# Voltage_Sense_0-30V.net
KiCad netlist of a schematic drawn in Altium Designer
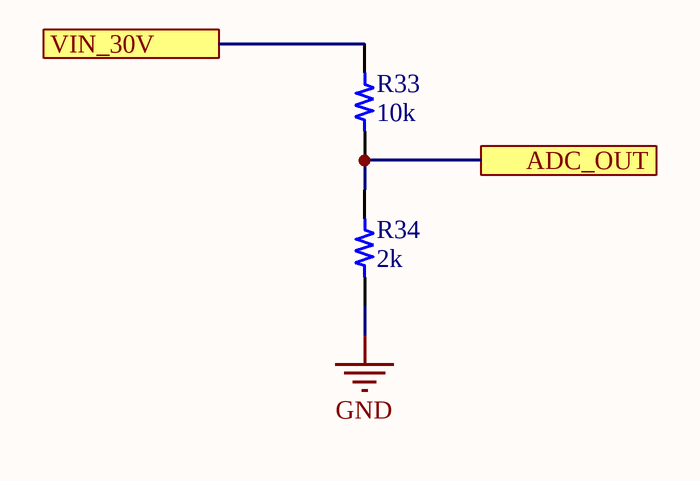
[diagram p0: Voltage_Sense_0-30V.SchDoc]

(export (version "E")
  (design (tool "Eeschema 10.0.6"))
  (components
    (comp (ref "R33")
      (value "10k")
      (footprint "RES 1206_3216")
      (description "RES 0.1 OHM 1% 1/2W 1206")
      (fields (field (name "PART NUMBER") "RL1206FR-7W0R1L") (field (name "MANUFACTURER") "Yageo"))
      (libsource (lib "Celestial Altium Library - altium_library") (part "Resistor"))
    )
    (comp (ref "R34")
      (value "2k")
      (footprint "RES 1206_3216")
      (description "RES 0.1 OHM 1% 1/2W 1206")
      (fields (field (name "PART NUMBER") "RL1206FR-7W0R1L") (field (name "MANUFACTURER") "Yageo"))
      (libsource (lib "Celestial Altium Library - altium_library") (part "Resistor"))
    )
  )
  (nets
    (net (code "1") (name "/ADC_OUT") (class "Default")
      (node (ref "R33") (pin "2") (pinfunction "2_2") (pintype "passive"))
      (node (ref "R34") (pin "1") (pinfunction "1_1") (pintype "passive"))
    )
    (net (code "2") (name "/VIN_30V") (class "Default")
      (node (ref "R33") (pin "1") (pinfunction "1_1") (pintype "passive"))
    )
    (net (code "3") (name "GND") (class "Default")
      (node (ref "R34") (pin "2") (pinfunction "2_2") (pintype "passive"))
    )
  )
)
